# schematic_easyeda.net
KiCad netlist of a schematic drawn in EasyEDA
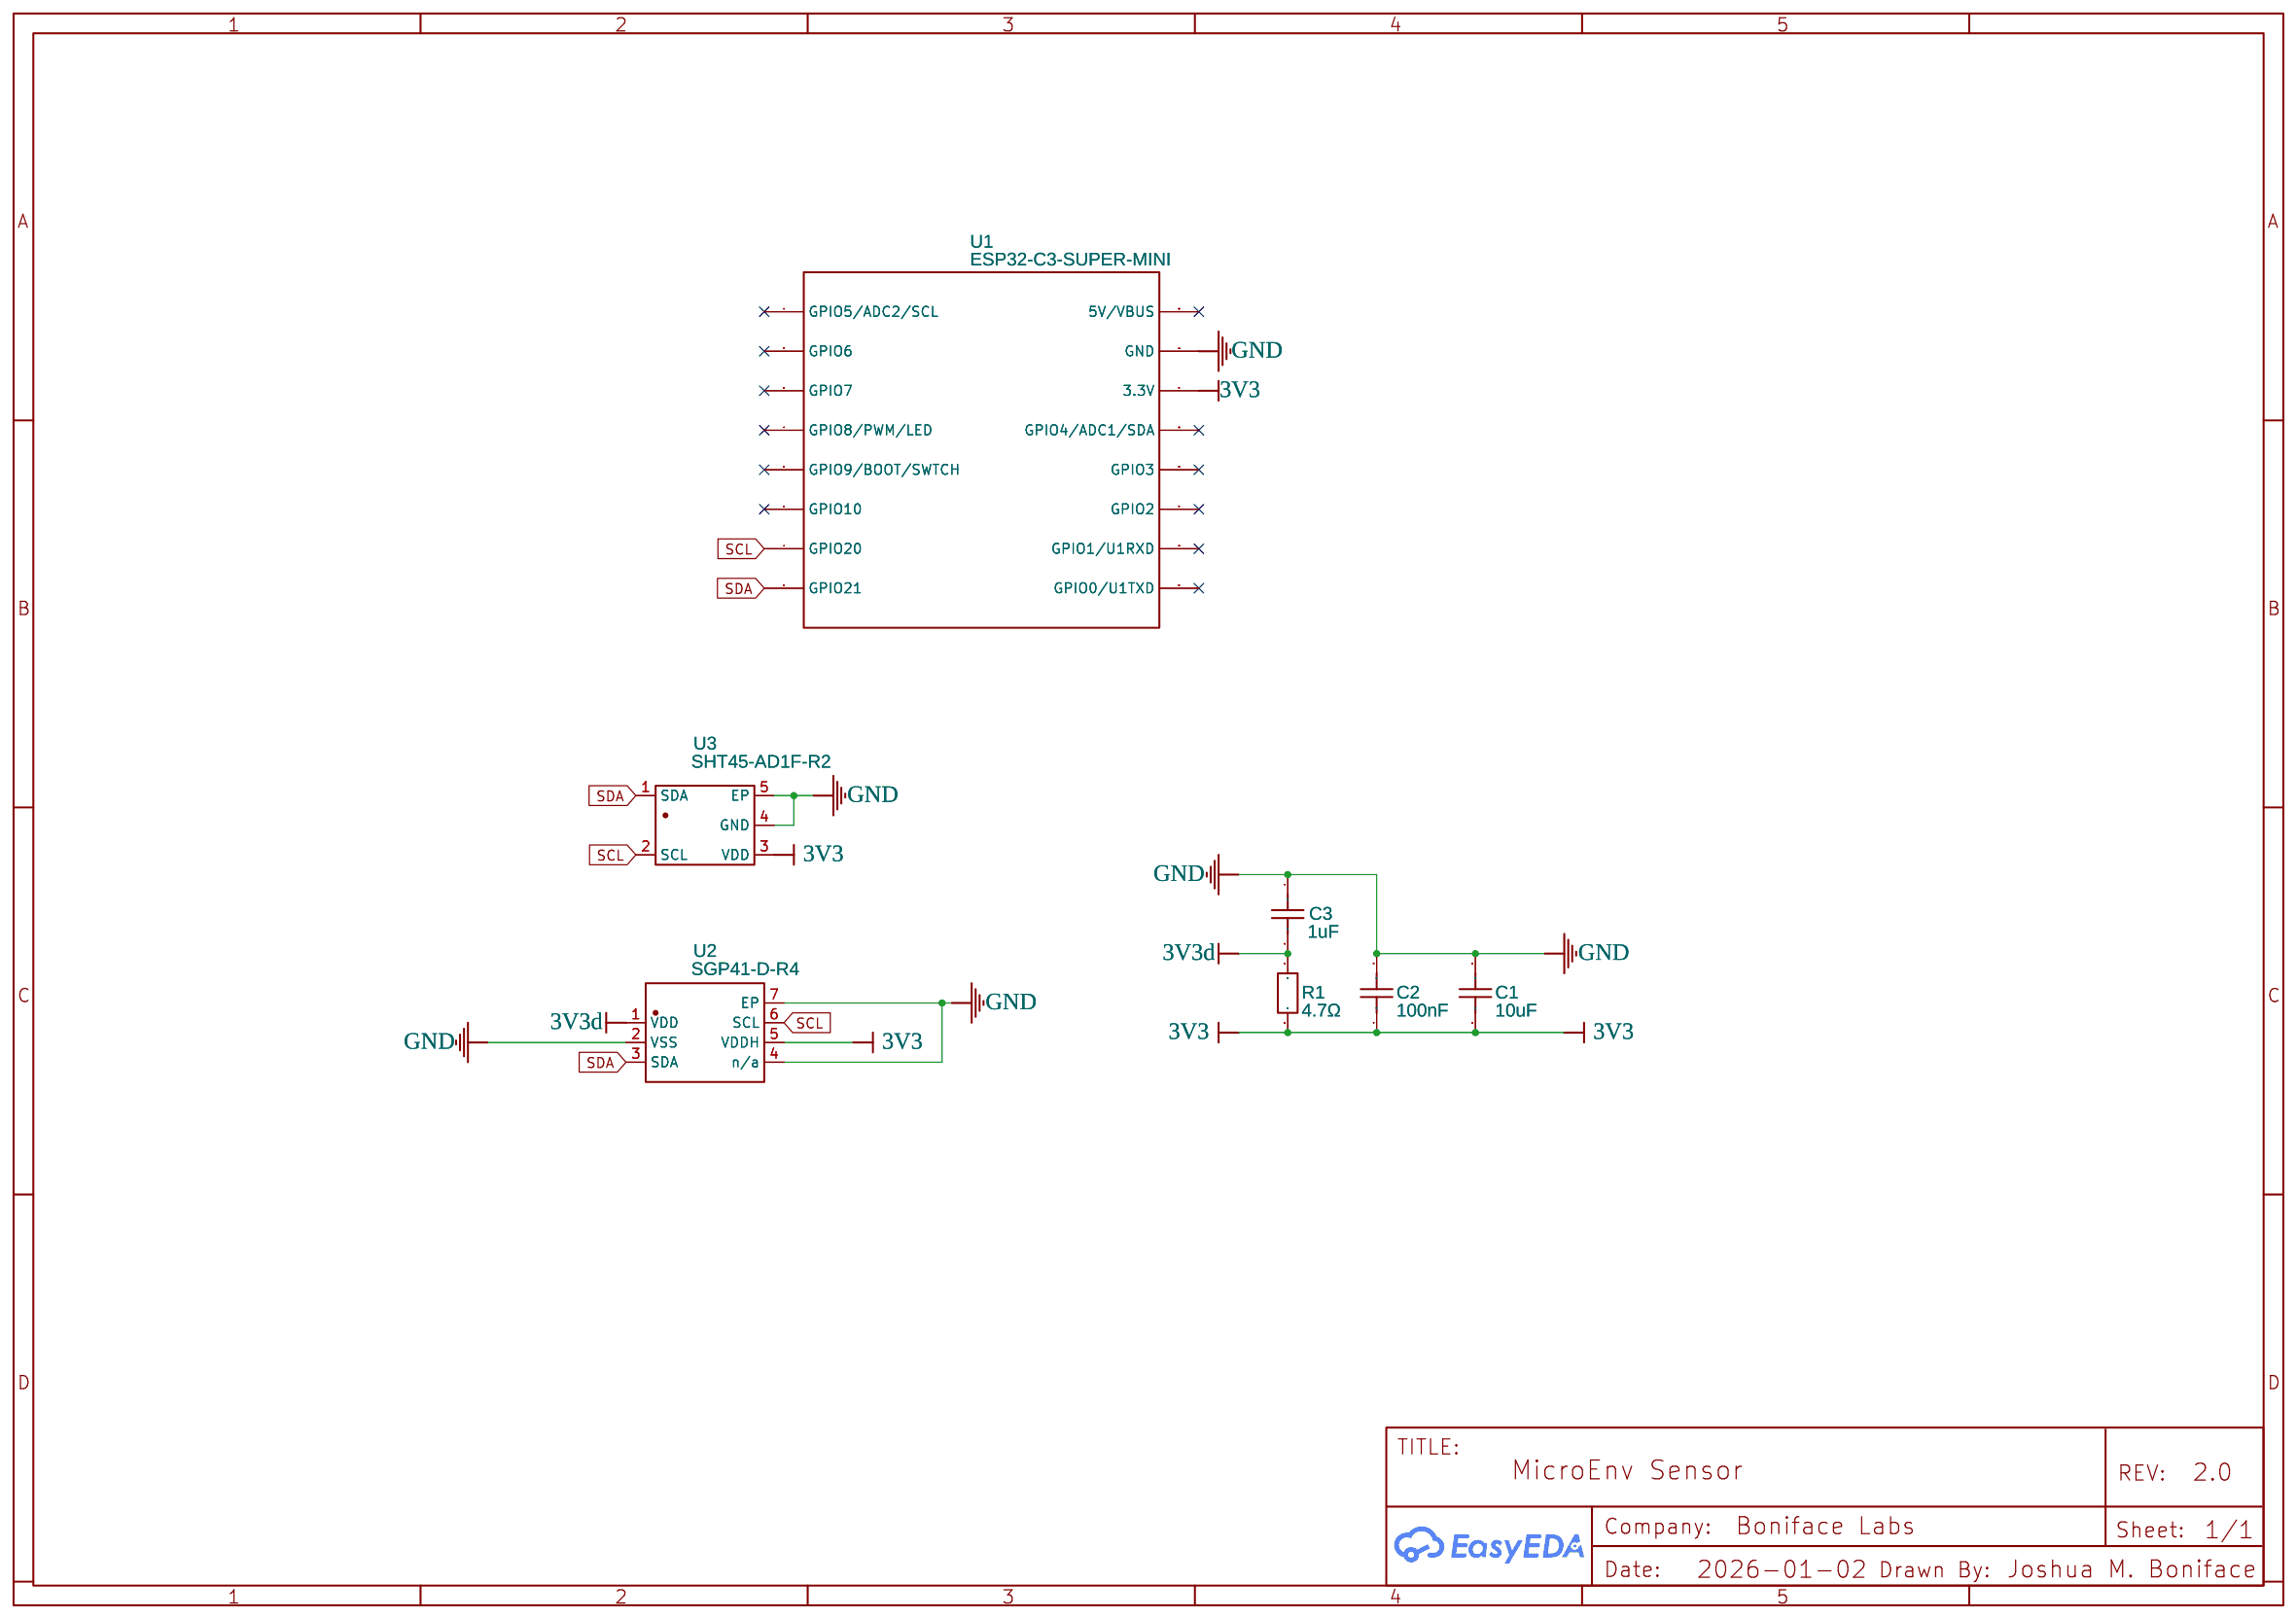
[diagram p0: schematic sheet]

(export (version "E")
  (design (tool "Eeschema 10.0.6"))
  (components
    (comp (ref "C1")
      (value "10uF")
      (fields (field (name "Manufacturer Part") "C2012JB1C106K125AB") (field (name "Manufacturer") "TDK"))
      (libsource (lib "") (part "C2012JB1C106K125AB"))
    )
    (comp (ref "C2")
      (value "100nF")
      (fields (field (name "Manufacturer Part") "C2012JB2A104K125AA") (field (name "Manufacturer") "TDK"))
      (libsource (lib "") (part "C2012JB2A104K125AA"))
    )
    (comp (ref "C3")
      (value "1uF")
      (fields (field (name "Manufacturer Part") "C2012X5R1E105K085AC") (field (name "Manufacturer") "TDK"))
      (libsource (lib "") (part "C2012X5R1E105K085AC"))
    )
    (comp (ref "R1")
      (value "4.7Ω")
      (fields
        (field (name "Manufacturer Part") "CRGP1206F4K7")
        (field (name "Manufacturer") "TE Connectivity(泰科电子)")
      )
      (libsource (lib "") (part "CRGP1206F4K7"))
    )
    (comp (ref "U1")
      (value "ESP32-C3-SUPER-MINI")
      (fields (field (name "Manufacturer") "Maker go"))
      (libsource (lib "") (part "ESP32-C3-SUPER-MINI"))
    )
    (comp (ref "U2")
      (value "SGP41-D-R4")
      (fields (field (name "Manufacturer") "Sensirion(瑞士盛思锐)"))
      (libsource (lib "") (part "SGP41-D-R4"))
    )
    (comp (ref "U3")
      (value "SHT45-AD1F-R2")
      (fields (field (name "Manufacturer") "Sensirion(瑞士盛思锐)"))
      (libsource (lib "") (part "SHT45-AD1F-R2"))
    )
  )
  (nets
    (net (code "1") (name "3V3") (class "Default")
      (node (ref "C1") (pin "1") (pinfunction "1_1") (pintype "unspecified"))
      (node (ref "C2") (pin "1") (pinfunction "1_1") (pintype "unspecified"))
      (node (ref "R1") (pin "2") (pinfunction "2_2") (pintype "unspecified"))
      (node (ref "U1") (pin "14") (pinfunction "3.3V_14") (pintype "unspecified"))
      (node (ref "U2") (pin "5") (pinfunction "VDDH_5") (pintype "unspecified"))
      (node (ref "U3") (pin "3") (pinfunction "VDD_3") (pintype "unspecified"))
    )
    (net (code "2") (name "3V3d") (class "Default")
      (node (ref "C3") (pin "2") (pinfunction "2_2") (pintype "unspecified"))
      (node (ref "R1") (pin "1") (pinfunction "1_1") (pintype "unspecified"))
      (node (ref "U2") (pin "1") (pinfunction "VDD_1") (pintype "unspecified"))
    )
    (net (code "3") (name "GND") (class "Default")
      (node (ref "C1") (pin "2") (pinfunction "2_2") (pintype "unspecified"))
      (node (ref "C2") (pin "2") (pinfunction "2_2") (pintype "unspecified"))
      (node (ref "C3") (pin "1") (pinfunction "1_1") (pintype "unspecified"))
      (node (ref "U1") (pin "15") (pinfunction "GND_15") (pintype "unspecified"))
      (node (ref "U2") (pin "2") (pinfunction "VSS_2") (pintype "unspecified"))
      (node (ref "U2") (pin "4") (pinfunction "n/a_4") (pintype "unspecified"))
      (node (ref "U2") (pin "7") (pinfunction "EP_7") (pintype "unspecified"))
      (node (ref "U3") (pin "4") (pinfunction "GND_4") (pintype "unspecified"))
      (node (ref "U3") (pin "5") (pinfunction "EP_5") (pintype "unspecified"))
    )
    (net (code "4") (name "SCL") (class "Default")
      (node (ref "U1") (pin "7") (pinfunction "GPIO20_7") (pintype "unspecified"))
      (node (ref "U2") (pin "6") (pinfunction "SCL_6") (pintype "unspecified"))
      (node (ref "U3") (pin "2") (pinfunction "SCL_2") (pintype "unspecified"))
    )
    (net (code "5") (name "SDA") (class "Default")
      (node (ref "U1") (pin "8") (pinfunction "GPIO21_8") (pintype "unspecified"))
      (node (ref "U2") (pin "3") (pinfunction "SDA_3") (pintype "unspecified"))
      (node (ref "U3") (pin "1") (pinfunction "SDA_1") (pintype "unspecified"))
    )
    (net (code "6") (name "unconnected-(U1-5V{slash}VBUS-Pad16)") (class "Default")
      (node (ref "U1") (pin "16") (pinfunction "5V/VBUS_16") (pintype "unspecified+no_connect"))
    )
    (net (code "7") (name "unconnected-(U1-GPIO0{slash}U1TXD-Pad9)") (class "Default")
      (node (ref "U1") (pin "9") (pinfunction "GPIO0/U1TXD_9") (pintype "unspecified+no_connect"))
    )
    (net (code "8") (name "unconnected-(U1-GPIO1{slash}U1RXD-Pad10)") (class "Default")
      (node (ref "U1") (pin "10") (pinfunction "GPIO1/U1RXD_10") (pintype "unspecified+no_connect"))
    )
    (net (code "9") (name "unconnected-(U1-GPIO2-Pad11)") (class "Default")
      (node (ref "U1") (pin "11") (pinfunction "GPIO2_11") (pintype "unspecified+no_connect"))
    )
    (net (code "10") (name "unconnected-(U1-GPIO3-Pad12)") (class "Default")
      (node (ref "U1") (pin "12") (pinfunction "GPIO3_12") (pintype "unspecified+no_connect"))
    )
    (net (code "11") (name "unconnected-(U1-GPIO4{slash}ADC1{slash}SDA-Pad13)") (class "Default")
      (node (ref "U1") (pin "13") (pinfunction "GPIO4/ADC1/SDA_13") (pintype "unspecified+no_connect"))
    )
    (net (code "12") (name "unconnected-(U1-GPIO5{slash}ADC2{slash}SCL-Pad1)") (class "Default")
      (node (ref "U1") (pin "1") (pinfunction "GPIO5/ADC2/SCL_1") (pintype "unspecified+no_connect"))
    )
    (net (code "13") (name "unconnected-(U1-GPIO6-Pad2)") (class "Default")
      (node (ref "U1") (pin "2") (pinfunction "GPIO6_2") (pintype "unspecified+no_connect"))
    )
    (net (code "14") (name "unconnected-(U1-GPIO7-Pad3)") (class "Default")
      (node (ref "U1") (pin "3") (pinfunction "GPIO7_3") (pintype "unspecified+no_connect"))
    )
    (net (code "15") (name "unconnected-(U1-GPIO8{slash}PWM{slash}LED-Pad4)") (class "Default")
      (node (ref "U1") (pin "4") (pinfunction "GPIO8/PWM/LED_4") (pintype "unspecified+no_connect"))
    )
    (net (code "16") (name "unconnected-(U1-GPIO9{slash}BOOT{slash}SWTCH-Pad5)") (class "Default")
      (node (ref "U1") (pin "5") (pinfunction "GPIO9/BOOT/SWTCH_5") (pintype "unspecified+no_connect"))
    )
    (net (code "17") (name "unconnected-(U1-GPIO10-Pad6)") (class "Default")
      (node (ref "U1") (pin "6") (pinfunction "GPIO10_6") (pintype "unspecified+no_connect"))
    )
  )
)
